# Sensor.net
KiCad netlist of a schematic drawn in Altium Designer
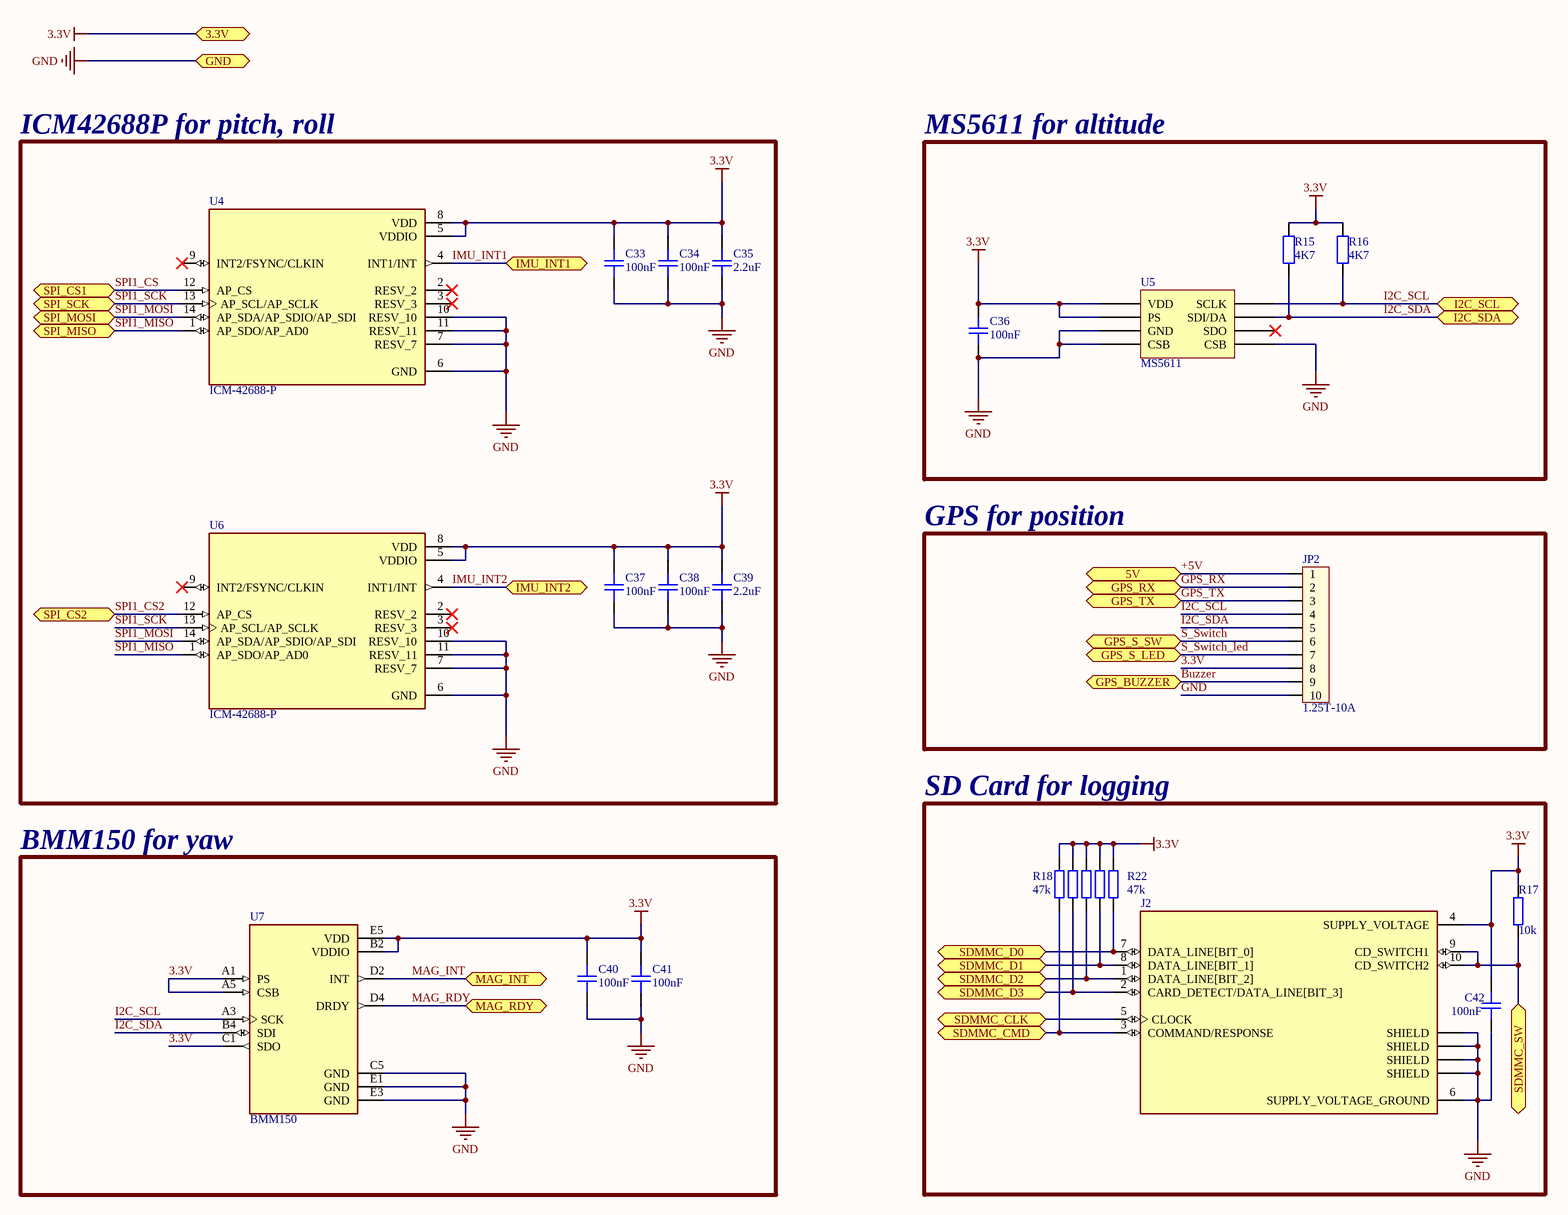
[diagram p0: Sensor.SchDoc]

(export (version "E")
  (design (tool "Eeschema 10.0.6"))
  (components
    (comp (ref "C33")
      (value "100nF")
      (footprint "CAP_0402")
      (description "0402 100nF 16V X7R")
      (libsource (lib "Schematic-Lib-PhilsLab") (part "CAP_0402"))
    )
    (comp (ref "C34")
      (value "100nF")
      (footprint "CAP_0402")
      (description "0402 100nF 16V X7R")
      (libsource (lib "Schematic-Lib-PhilsLab") (part "CAP_0402"))
    )
    (comp (ref "C35")
      (value "2.2uF")
      (footprint "CAP_0603")
      (description "0603 2.2uF 10V X7R")
      (libsource (lib "Schematic-Lib-PhilsLab") (part "CAP_0603"))
    )
    (comp (ref "C36")
      (value "100nF")
      (footprint "CAP_0402")
      (description "0402 100nF 16V X7R")
      (libsource (lib "Schematic-Lib-PhilsLab") (part "CAP_0402"))
    )
    (comp (ref "C37")
      (value "100nF")
      (footprint "CAP_0402")
      (description "0402 100nF 16V X7R")
      (libsource (lib "Schematic-Lib-PhilsLab") (part "CAP_0402"))
    )
    (comp (ref "C38")
      (value "100nF")
      (footprint "CAP_0402")
      (description "0402 100nF 16V X7R")
      (libsource (lib "Schematic-Lib-PhilsLab") (part "CAP_0402"))
    )
    (comp (ref "C39")
      (value "2.2uF")
      (footprint "CAP_0603")
      (description "0603 2.2uF 10V X7R")
      (libsource (lib "Schematic-Lib-PhilsLab") (part "CAP_0603"))
    )
    (comp (ref "C40")
      (value "100nF")
      (footprint "CAP_0402")
      (description "0402 100nF 16V X7R")
      (libsource (lib "Schematic-Lib-PhilsLab") (part "CAP_0402"))
    )
    (comp (ref "C41")
      (value "100nF")
      (footprint "CAP_0402")
      (description "0402 100nF 16V X7R")
      (libsource (lib "Schematic-Lib-PhilsLab") (part "CAP_0402"))
    )
    (comp (ref "C42")
      (value "100nF")
      (footprint "CAP_0402")
      (description "0402 100nF 16V X7R")
      (libsource (lib "Schematic-Lib-PhilsLab") (part "CAP_0402"))
    )
    (comp (ref "J2")
      (value "~")
      (footprint "AMPHENOL_1140084168")
      (fields (field (name "MF") "amphenol communications solutions") (field (name "MP") "114-00841-68.."))
      (libsource (lib "1140084168") (part "1140084168"))
    )
    (comp (ref "JP2")
      (value "1.25T-10A")
      (footprint "BM10B-GHS-TBT")
      (description "Cắm")
      (libsource (lib "THU VIEN SCH") (part "Header 1_2.54_10P"))
    )
    (comp (ref "R15")
      (value "4K7")
      (footprint "RESC-0402 (1005)")
      (description "RES SMD 4.7K OHM 1% 1/10W 0603")
      (fields (field (name "MPN") "RC0603FR-074K7L"))
      (libsource (lib "BYTECH_HW_LIB_2019 (1)") (part "RC0603FR-074K7L"))
    )
    (comp (ref "R16")
      (value "4K7")
      (footprint "RESC-0402 (1005)")
      (description "RES SMD 4.7K OHM 1% 1/10W 0603")
      (fields (field (name "MPN") "RC0603FR-074K7L"))
      (libsource (lib "BYTECH_HW_LIB_2019 (1)") (part "RC0603FR-074K7L"))
    )
    (comp (ref "R17")
      (value "10k")
      (footprint "RES_0402")
      (description "Resistor SMD 0402")
      (libsource (lib "Schematic-Lib-PhilsLab") (part "RES_0402"))
    )
    (comp (ref "R18")
      (value "47k")
      (footprint "RES_0402")
      (description "Resistor SMD 0402")
      (libsource (lib "Schematic-Lib-PhilsLab") (part "RES_0402"))
    )
    (comp (ref "R19")
      (value "47k")
      (footprint "RES_0402")
      (description "Resistor SMD 0402")
      (libsource (lib "Schematic-Lib-PhilsLab") (part "RES_0402"))
    )
    (comp (ref "R20")
      (value "47k")
      (footprint "RES_0402")
      (description "Resistor SMD 0402")
      (libsource (lib "Schematic-Lib-PhilsLab") (part "RES_0402"))
    )
    (comp (ref "R21")
      (value "47k")
      (footprint "RES_0402")
      (description "Resistor SMD 0402")
      (libsource (lib "Schematic-Lib-PhilsLab") (part "RES_0402"))
    )
    (comp (ref "R22")
      (value "47k")
      (footprint "RES_0402")
      (description "Resistor SMD 0402")
      (libsource (lib "Schematic-Lib-PhilsLab") (part "RES_0402"))
    )
    (comp (ref "U4")
      (value "ICM-42688-P")
      (footprint "PCB1:PQFN50P300X250X97-14N")
      (description "Accelerometer, Gyroscope, 6 Axis Sensor Output")
      (libsource (lib "ICM-42688-P") (part "ICM-42688-P"))
    )
    (comp (ref "U5") (value "MS5611") (footprint "MS5611_1") (libsource (lib "Schlib1") (part "MS5611")))
    (comp (ref "U6")
      (value "ICM-42688-P")
      (footprint "PCB1:PQFN50P300X250X97-14N")
      (description "Accelerometer, Gyroscope, 6 Axis Sensor Output")
      (libsource (lib "ICM-42688-P") (part "ICM-42688-P"))
    )
    (comp (ref "U7")
      (value "BMM150")
      (footprint "PCB1:XDCR_BMM150")
      (description "FlipCore, Hall Effect Sensor X, Y, Z Axis 12-WLCSP (1.56x1.56)")
      (fields (field (name "MF") "Bosch Sensortec"))
      (libsource (lib "BMM150") (part "BMM150"))
    )
  )
  (nets
    (net (code "1") (name "/+5V") (class "Default")
      (node (ref "JP2") (pin "1") (pinfunction "1_1") (pintype "passive"))
    )
    (net (code "3") (name "/Buzzer") (class "Default")
      (node (ref "JP2") (pin "9") (pinfunction "9_9") (pintype "passive"))
    )
    (net (code "4") (name "/GPS_RX") (class "Default")
      (node (ref "JP2") (pin "2") (pinfunction "2_2") (pintype "passive"))
    )
    (net (code "5") (name "/GPS_TX") (class "Default")
      (node (ref "JP2") (pin "3") (pinfunction "3_3") (pintype "passive"))
    )
    (net (code "6") (name "/I2C_SCL") (class "Default")
      (node (ref "JP2") (pin "4") (pinfunction "4_4") (pintype "passive"))
      (node (ref "R16") (pin "1") (pinfunction "1_1") (pintype "passive"))
      (node (ref "U5") (pin "135") (pinfunction "SCLK_135") (pintype "passive"))
      (node (ref "U7") (pin "A3") (pinfunction "SCK_A3") (pintype "input"))
    )
    (net (code "7") (name "/I2C_SDA") (class "Default")
      (node (ref "JP2") (pin "5") (pinfunction "5_5") (pintype "passive"))
      (node (ref "R15") (pin "1") (pinfunction "1_1") (pintype "passive"))
      (node (ref "U5") (pin "134") (pinfunction "SDI/DA_134") (pintype "passive"))
      (node (ref "U7") (pin "B4") (pinfunction "SDI_B4") (pintype "bidirectional"))
    )
    (net (code "8") (name "/IMU_INT1") (class "Default")
      (node (ref "U4") (pin "4") (pinfunction "INT1/INT_4") (pintype "output"))
    )
    (net (code "9") (name "/IMU_INT2") (class "Default")
      (node (ref "U6") (pin "4") (pinfunction "INT1/INT_4") (pintype "output"))
    )
    (net (code "10") (name "/MAG_INT") (class "Default")
      (node (ref "U7") (pin "D2") (pinfunction "INT_D2") (pintype "output"))
    )
    (net (code "11") (name "/MAG_RDY") (class "Default")
      (node (ref "U7") (pin "D4") (pinfunction "DRDY_D4") (pintype "output"))
    )
    (net (code "12") (name "/SDMMC_CLK") (class "Default")
      (node (ref "J2") (pin "5") (pinfunction "CLOCK_5") (pintype "bidirectional"))
    )
    (net (code "13") (name "/SDMMC_CMD") (class "Default")
      (node (ref "J2") (pin "3") (pinfunction "COMMAND/RESPONSE_3") (pintype "bidirectional"))
      (node (ref "R18") (pin "1") (pinfunction "1_1") (pintype "passive"))
    )
    (net (code "14") (name "/SDMMC_D0") (class "Default")
      (node (ref "J2") (pin "7") (pinfunction "DATA_LINE[BIT_0]_7") (pintype "bidirectional"))
      (node (ref "R22") (pin "1") (pinfunction "1_1") (pintype "passive"))
    )
    (net (code "15") (name "/SDMMC_D1") (class "Default")
      (node (ref "J2") (pin "8") (pinfunction "DATA_LINE[BIT_1]_8") (pintype "bidirectional"))
      (node (ref "R21") (pin "1") (pinfunction "1_1") (pintype "passive"))
    )
    (net (code "16") (name "/SDMMC_D2") (class "Default")
      (node (ref "J2") (pin "1") (pinfunction "DATA_LINE[BIT_2]_1") (pintype "bidirectional"))
      (node (ref "R20") (pin "1") (pinfunction "1_1") (pintype "passive"))
    )
    (net (code "17") (name "/SDMMC_D3") (class "Default")
      (node (ref "J2") (pin "2") (pinfunction "CARD_DETECT/DATA_LINE[BIT_3]_2") (pintype "bidirectional"))
      (node (ref "R19") (pin "1") (pinfunction "1_1") (pintype "passive"))
    )
    (net (code "18") (name "/SDMMC_SW") (class "Default")
      (node (ref "J2") (pin "10") (pinfunction "CD_SWITCH2_10") (pintype "bidirectional"))
      (node (ref "J2") (pin "9") (pinfunction "CD_SWITCH1_9") (pintype "bidirectional"))
      (node (ref "R17") (pin "1") (pinfunction "1_1") (pintype "passive"))
    )
    (net (code "19") (name "/SPI1_CS") (class "Default")
      (node (ref "U4") (pin "12") (pinfunction "AP_CS_12") (pintype "input"))
    )
    (net (code "20") (name "/SPI1_CS2") (class "Default")
      (node (ref "U6") (pin "12") (pinfunction "AP_CS_12") (pintype "input"))
    )
    (net (code "21") (name "/SPI1_MISO") (class "Default")
      (node (ref "U4") (pin "1") (pinfunction "AP_SDO/AP_AD0_1") (pintype "bidirectional"))
      (node (ref "U6") (pin "1") (pinfunction "AP_SDO/AP_AD0_1") (pintype "bidirectional"))
    )
    (net (code "22") (name "/SPI1_MOSI") (class "Default")
      (node (ref "U4") (pin "14") (pinfunction "AP_SDA/AP_SDIO/AP_SDI_14") (pintype "bidirectional"))
      (node (ref "U6") (pin "14") (pinfunction "AP_SDA/AP_SDIO/AP_SDI_14") (pintype "bidirectional"))
    )
    (net (code "23") (name "/SPI1_SCK") (class "Default")
      (node (ref "U4") (pin "13") (pinfunction "AP_SCL/AP_SCLK_13") (pintype "input"))
      (node (ref "U6") (pin "13") (pinfunction "AP_SCL/AP_SCLK_13") (pintype "input"))
    )
    (net (code "24") (name "/S_Switch") (class "Default")
      (node (ref "JP2") (pin "6") (pinfunction "6_6") (pintype "passive"))
    )
    (net (code "25") (name "/S_Switch_led") (class "Default")
      (node (ref "JP2") (pin "7") (pinfunction "7_7") (pintype "passive"))
    )
    (net (code "26") (name "3.3V") (class "Default")
      (node (ref "C33") (pin "2") (pinfunction "2_2") (pintype "passive"))
      (node (ref "C34") (pin "2") (pinfunction "2_2") (pintype "passive"))
      (node (ref "C35") (pin "2") (pinfunction "2_2") (pintype "passive"))
      (node (ref "C36") (pin "2") (pinfunction "2_2") (pintype "passive"))
      (node (ref "C37") (pin "2") (pinfunction "2_2") (pintype "passive"))
      (node (ref "C38") (pin "2") (pinfunction "2_2") (pintype "passive"))
      (node (ref "C39") (pin "2") (pinfunction "2_2") (pintype "passive"))
      (node (ref "C40") (pin "2") (pinfunction "2_2") (pintype "passive"))
      (node (ref "C41") (pin "2") (pinfunction "2_2") (pintype "passive"))
      (node (ref "C42") (pin "2") (pinfunction "2_2") (pintype "passive"))
      (node (ref "J2") (pin "4") (pinfunction "SUPPLY_VOLTAGE_4") (pintype "power_in"))
      (node (ref "JP2") (pin "8") (pinfunction "8_8") (pintype "passive"))
      (node (ref "R15") (pin "2") (pinfunction "2_2") (pintype "passive"))
      (node (ref "R16") (pin "2") (pinfunction "2_2") (pintype "passive"))
      (node (ref "R17") (pin "2") (pinfunction "2_2") (pintype "passive"))
      (node (ref "R18") (pin "2") (pinfunction "2_2") (pintype "passive"))
      (node (ref "R19") (pin "2") (pinfunction "2_2") (pintype "passive"))
      (node (ref "R20") (pin "2") (pinfunction "2_2") (pintype "passive"))
      (node (ref "R21") (pin "2") (pinfunction "2_2") (pintype "passive"))
      (node (ref "R22") (pin "2") (pinfunction "2_2") (pintype "passive"))
      (node (ref "U4") (pin "5") (pinfunction "VDDIO_5") (pintype "power_in"))
      (node (ref "U4") (pin "8") (pinfunction "VDD_8") (pintype "power_in"))
      (node (ref "U5") (pin "128") (pinfunction "VDD_128") (pintype "passive"))
      (node (ref "U5") (pin "129") (pinfunction "PS_129") (pintype "passive"))
      (node (ref "U6") (pin "5") (pinfunction "VDDIO_5") (pintype "power_in"))
      (node (ref "U6") (pin "8") (pinfunction "VDD_8") (pintype "power_in"))
      (node (ref "U7") (pin "A1") (pinfunction "PS_A1") (pintype "input"))
      (node (ref "U7") (pin "A5") (pinfunction "CSB_A5") (pintype "input"))
      (node (ref "U7") (pin "B2") (pinfunction "VDDIO_B2") (pintype "power_in"))
      (node (ref "U7") (pin "C1") (pinfunction "SDO_C1") (pintype "output"))
      (node (ref "U7") (pin "E5") (pinfunction "VDD_E5") (pintype "power_in"))
    )
    (net (code "27") (name "GND") (class "Default")
      (node (ref "C33") (pin "1") (pinfunction "1_1") (pintype "passive"))
      (node (ref "C34") (pin "1") (pinfunction "1_1") (pintype "passive"))
      (node (ref "C35") (pin "1") (pinfunction "1_1") (pintype "passive"))
      (node (ref "C36") (pin "1") (pinfunction "1_1") (pintype "passive"))
      (node (ref "C37") (pin "1") (pinfunction "1_1") (pintype "passive"))
      (node (ref "C38") (pin "1") (pinfunction "1_1") (pintype "passive"))
      (node (ref "C39") (pin "1") (pinfunction "1_1") (pintype "passive"))
      (node (ref "C40") (pin "1") (pinfunction "1_1") (pintype "passive"))
      (node (ref "C41") (pin "1") (pinfunction "1_1") (pintype "passive"))
      (node (ref "C42") (pin "1") (pinfunction "1_1") (pintype "passive"))
      (node (ref "J2") (pin "6") (pinfunction "SUPPLY_VOLTAGE_GROUND_6") (pintype "power_in"))
      (node (ref "J2") (pin "S1") (pinfunction "SHIELD_S1") (pintype "passive"))
      (node (ref "J2") (pin "S2") (pinfunction "SHIELD_S2") (pintype "passive"))
      (node (ref "J2") (pin "S3") (pinfunction "SHIELD_S3") (pintype "passive"))
      (node (ref "J2") (pin "S4") (pinfunction "SHIELD_S4") (pintype "passive"))
      (node (ref "JP2") (pin "10") (pinfunction "10_10") (pintype "passive"))
      (node (ref "U4") (pin "10") (pinfunction "RESV_10_10") (pintype "passive"))
      (node (ref "U4") (pin "11") (pinfunction "RESV_11_11") (pintype "passive"))
      (node (ref "U4") (pin "6") (pinfunction "GND_6") (pintype "power_in"))
      (node (ref "U4") (pin "7") (pinfunction "RESV_7_7") (pintype "passive"))
      (node (ref "U5") (pin "130") (pinfunction "GND_130") (pintype "passive"))
      (node (ref "U5") (pin "131") (pinfunction "CSB_131") (pintype "passive"))
      (node (ref "U5") (pin "132") (pinfunction "CSB_132") (pintype "passive"))
      (node (ref "U6") (pin "10") (pinfunction "RESV_10_10") (pintype "passive"))
      (node (ref "U6") (pin "11") (pinfunction "RESV_11_11") (pintype "passive"))
      (node (ref "U6") (pin "6") (pinfunction "GND_6") (pintype "power_in"))
      (node (ref "U6") (pin "7") (pinfunction "RESV_7_7") (pintype "passive"))
      (node (ref "U7") (pin "C5") (pinfunction "GND_C5") (pintype "power_in"))
      (node (ref "U7") (pin "E1") (pinfunction "GND_E1") (pintype "power_in"))
      (node (ref "U7") (pin "E3") (pinfunction "GND_E3") (pintype "power_in"))
    )
    (net (code "28") (name "unconnected-(U4-INT2{slash}FSYNC{slash}CLKIN-Pad9)") (class "Default")
      (node (ref "U4") (pin "9") (pinfunction "INT2/FSYNC/CLKIN_9") (pintype "bidirectional+no_connect"))
    )
    (net (code "29") (name "unconnected-(U4-RESV_2-Pad2)") (class "Default")
      (node (ref "U4") (pin "2") (pinfunction "RESV_2_2") (pintype "passive+no_connect"))
    )
    (net (code "30") (name "unconnected-(U4-RESV_3-Pad3)") (class "Default")
      (node (ref "U4") (pin "3") (pinfunction "RESV_3_3") (pintype "passive+no_connect"))
    )
    (net (code "31") (name "unconnected-(U5-SDO-Pad133)") (class "Default")
      (node (ref "U5") (pin "133") (pinfunction "SDO_133") (pintype "passive+no_connect"))
    )
    (net (code "32") (name "unconnected-(U6-INT2{slash}FSYNC{slash}CLKIN-Pad9)") (class "Default")
      (node (ref "U6") (pin "9") (pinfunction "INT2/FSYNC/CLKIN_9") (pintype "bidirectional+no_connect"))
    )
    (net (code "33") (name "unconnected-(U6-RESV_2-Pad2)") (class "Default")
      (node (ref "U6") (pin "2") (pinfunction "RESV_2_2") (pintype "passive+no_connect"))
    )
    (net (code "34") (name "unconnected-(U6-RESV_3-Pad3)") (class "Default")
      (node (ref "U6") (pin "3") (pinfunction "RESV_3_3") (pintype "passive+no_connect"))
    )
  )
)
